# ESP_OBD_Handheld.net
KiCad netlist of a schematic drawn in Altium Designer
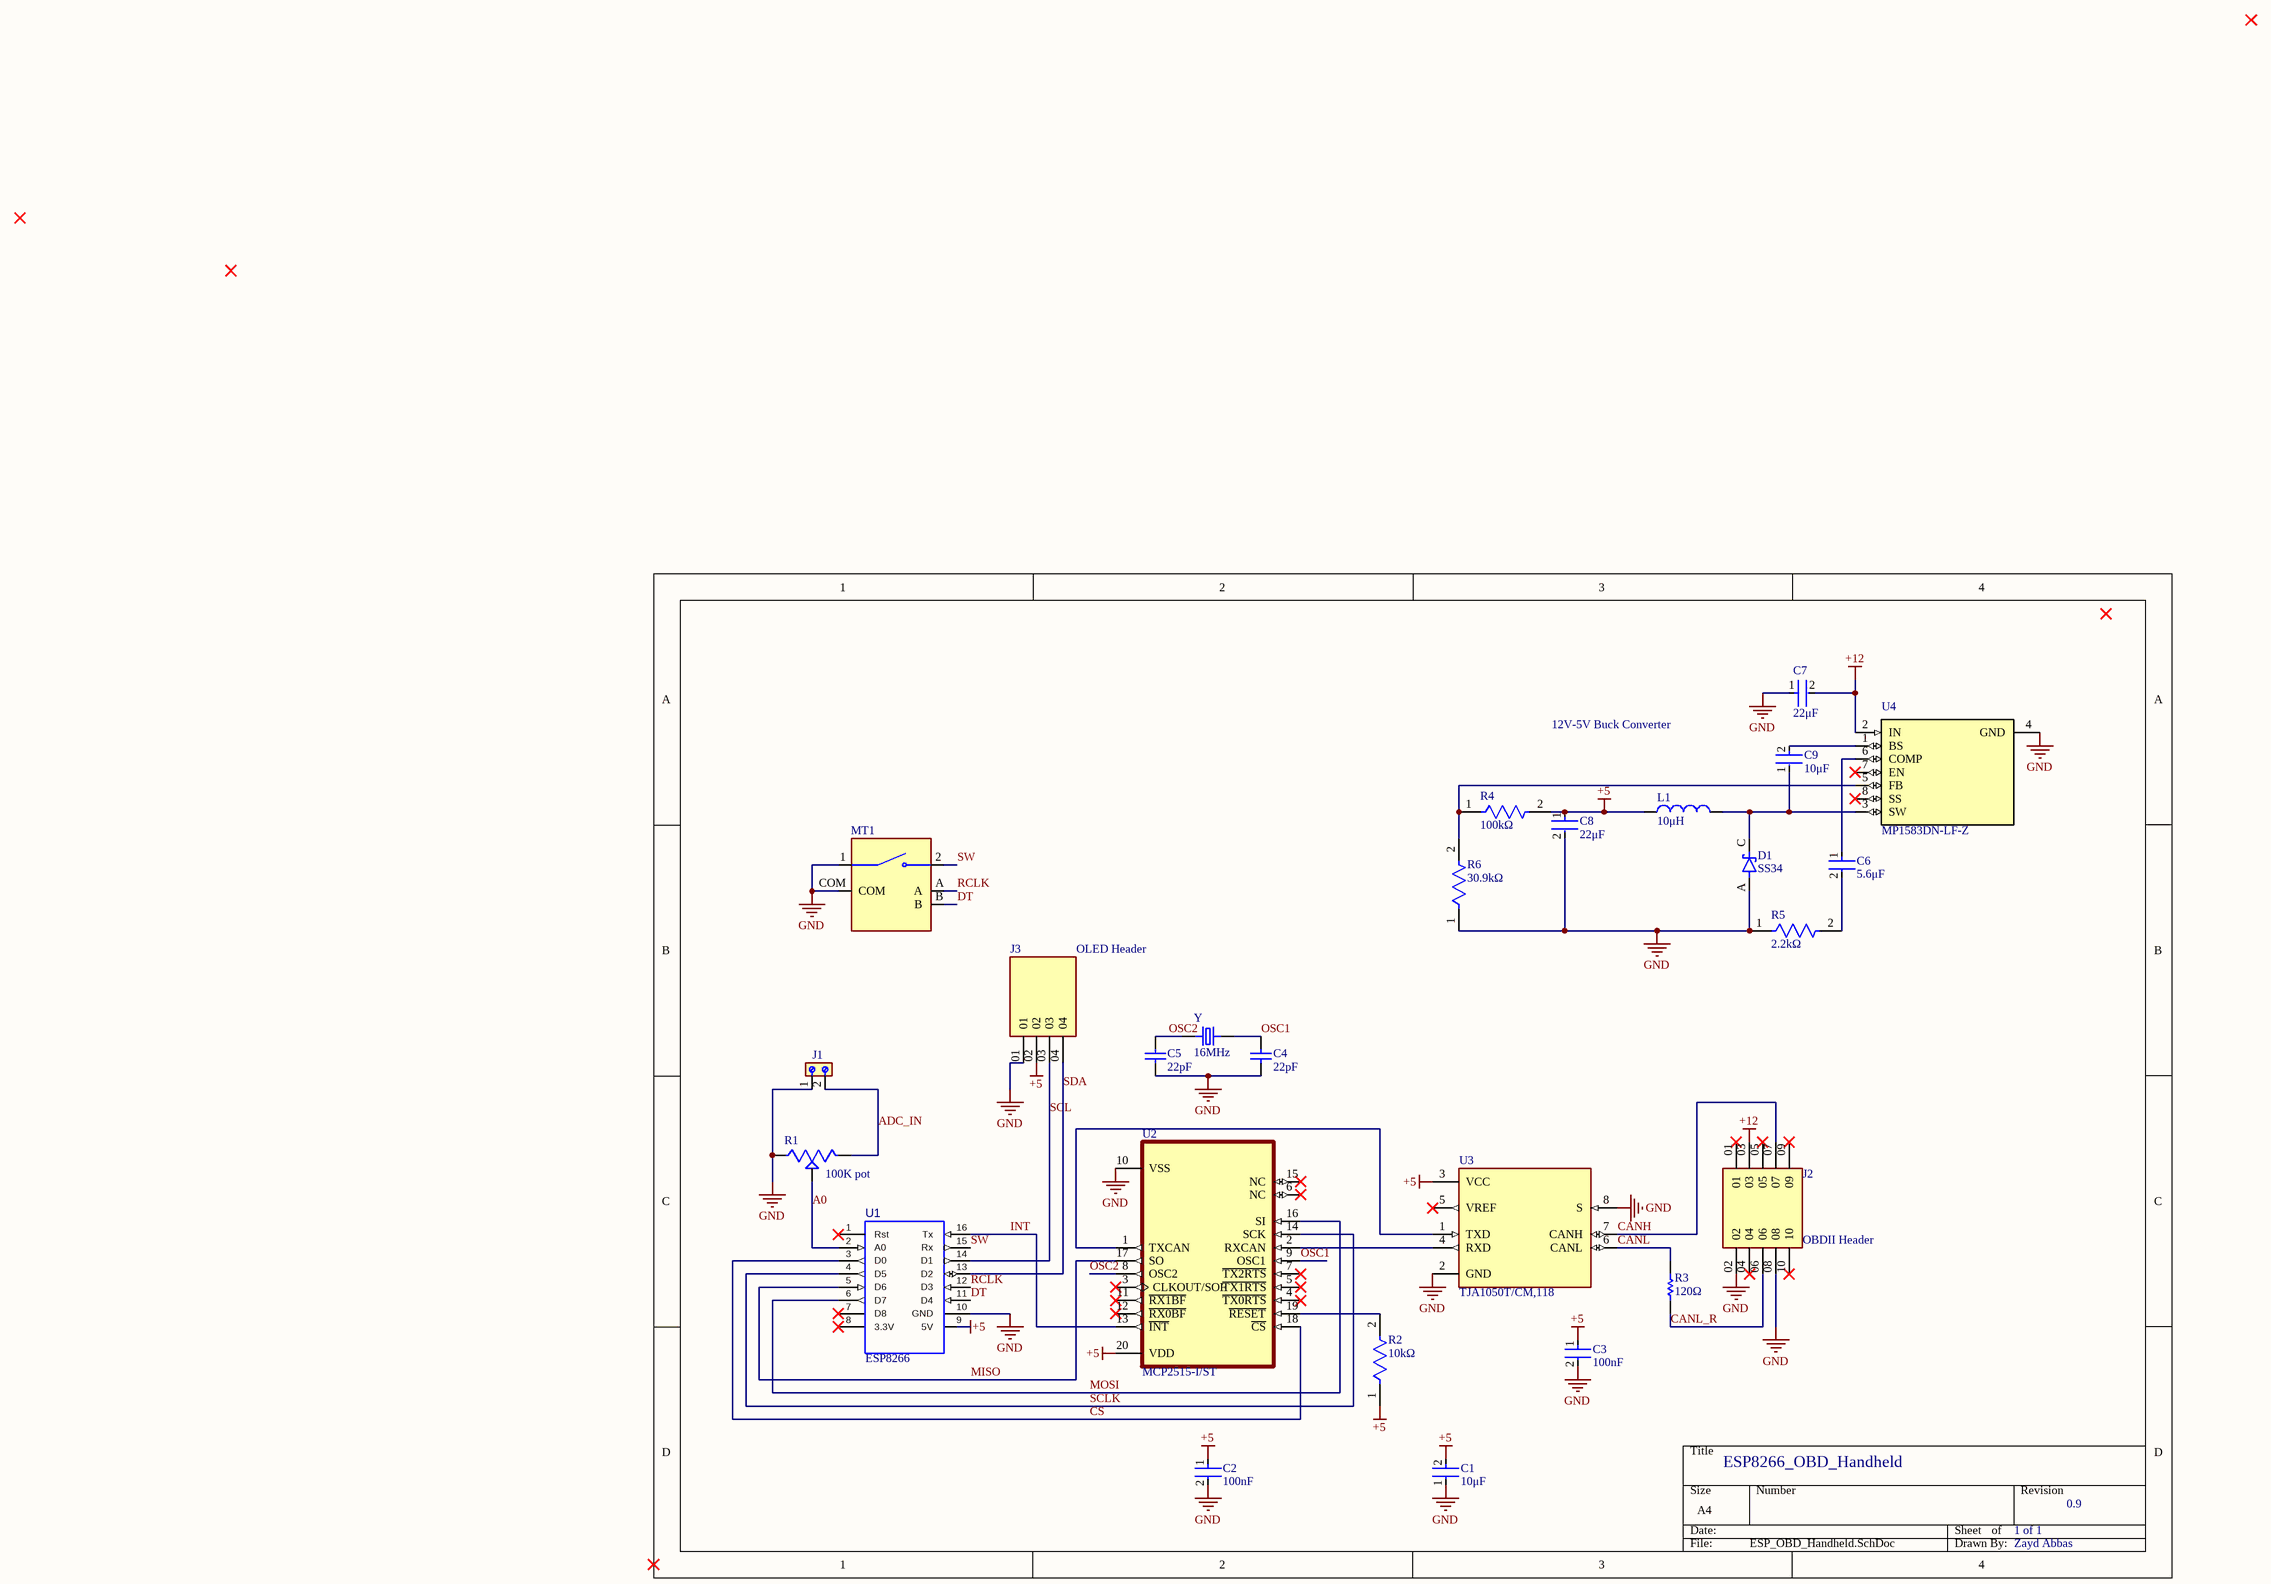
[diagram p0: ESP_OBD_Handheld.SchDoc]

(export (version "E")
  (design (tool "Eeschema 10.0.6"))
  (components
    (comp (ref "C1")
      (value "10μF")
      (footprint "FP-C1608-080-0_1-MFG")
      (description "Multilayer Ceramic Capacitors 10μF ±10% 10V X5R SMD 0603")
      (fields (field (name "VOLTAGE") "10V") (field (name "TOLERANCE") "10%"))
      (libsource (lib "Components - 15.01.23 - 12.48") (part "CMP-2000-04979-3"))
    )
    (comp (ref "C2")
      (value "100nF")
      (footprint "FP-CGA3E-0_3-0_1-IPC_C")
      (description "Cap Ceramic 100nF 50V X7R 10% Pad SMD 0603 +125°C Automotive T/R")
      (fields (field (name "TOLERANCE") "10%") (field (name "VOLTAGE") "50V"))
      (libsource (lib "Components - 15.01.23 - 13.18") (part "CMP-2000-07546-2"))
    )
    (comp (ref "C3")
      (value "100nF")
      (footprint "FP-CGA3E-0_3-0_1-IPC_C")
      (description "Cap Ceramic 100nF 50V X7R 10% Pad SMD 0603 +125°C Automotive T/R")
      (fields (field (name "TOLERANCE") "10%") (field (name "VOLTAGE") "50V"))
      (libsource (lib "Components - 15.01.23 - 13.18") (part "CMP-2000-07546-2"))
    )
    (comp (ref "C4")
      (value "22pF")
      (footprint "CAPC1608X90X35LL10T15")
      (description "Chip Capacitor, 22 pF, +/- 5%, 50 V, -55 to 125 degC, 0603 (1608 Metric), RoHS, Tape and Reel")
      (fields (field (name "MANUFACTURER") "Murata"))
      (libsource (lib "Components - 15.01.23 - 02.22") (part "CMP-2000-04945-1"))
    )
    (comp (ref "C5")
      (value "22pF")
      (footprint "CAPC1608X90X35LL10T15")
      (description "Chip Capacitor, 22 pF, +/- 5%, 50 V, -55 to 125 degC, 0603 (1608 Metric), RoHS, Tape and Reel")
      (fields (field (name "MANUFACTURER") "Murata"))
      (libsource (lib "Components - 15.01.23 - 02.22") (part "CMP-2000-04945-1"))
    )
    (comp (ref "C6")
      (value "5.6μF")
      (footprint "FP-CC0603-DA-IPC_B")
      (description "Surface Mount Ceramic Multilayer Capacitor 0.0056uF 10% X7R 50V 0603 Paper T/R")
      (fields
        (field (name "MANUFACTURER PART NUMBER") "CC0603KRX7R9BB562")
        (field (name "MANUFACTURER") "YAGEO")
      )
      (libsource (lib "Components - 15.01.23 - 13.23") (part "CMP-03422-001341-1"))
    )
    (comp (ref "C7")
      (value "22μF")
      (footprint "FP-C2012-125-0_2-MFG")
      (description "Multilayer Ceramic Capacitors 22μF ±10% 16V X5R SMD 0805")
      (fields (field (name "TOLERANCE") "10%") (field (name "VOLTAGE") "16V"))
      (libsource (lib "Components - 15.01.23 - 13.25") (part "CMP-2000-06037-3"))
    )
    (comp (ref "C8")
      (value "22μF")
      (footprint "FP-C2012-125-0_2-MFG")
      (description "Multilayer Ceramic Capacitors 22μF ±10% 16V X5R SMD 0805")
      (fields (field (name "TOLERANCE") "10%") (field (name "VOLTAGE") "16V"))
      (libsource (lib "Components - 15.01.23 - 13.25") (part "CMP-2000-06037-3"))
    )
    (comp (ref "C9")
      (value "10μF")
      (footprint "FP-C1608-080-0_1-MFG")
      (description "Multilayer Ceramic Capacitors 10μF ±10% 10V X5R SMD 0603")
      (fields (field (name "VOLTAGE") "10V") (field (name "TOLERANCE") "10%"))
      (libsource (lib "Components - 15.01.23 - 12.48") (part "CMP-2000-04979-3"))
    )
    (comp (ref "D1")
      (value "SS34")
      (footprint "DIOM7959X265N")
      (description "Diode Schottky 40 V 3A Surface Mount SMC (DO-214AB)")
      (fields (field (name "MF") "ON Semiconductor"))
      (libsource (lib "SS34") (part "SS34"))
    )
    (comp (ref "J1")
      (value "691102710002")
      (footprint "691102710002")
      (description "2 Position Wire to Board Terminal Block Horizontal with Board 0.197 (5.00mm) Through Hole")
      (fields (field (name "MF") "Wurth Elektronik"))
      (libsource (lib "691102710002") (part "691102710002"))
    )
    (comp (ref "J2")
      (value "TSW-105-05-G-D")
      (footprint "SAMTEC_TSW-105-05-G-D")
      (fields (field (name "MF") "Samtec"))
      (libsource (lib "TSW-105-05-G-D") (part "TSW-105-05-G-D"))
    )
    (comp (ref "J3")
      (value "TLW-104-05-G-S")
      (footprint "SAMTEC_TLW-104-05-G-S")
      (libsource (lib "TLW-104-05-G-S") (part "TLW-104-05-G-S"))
    )
    (comp (ref "L1")
      (value "10μH")
      (footprint "VISH-IHLP2525C-01_V")
      (fields (field (name "MANUFACTURER") "Vishay") (field (name "TOLERANCE") "20%"))
      (libsource (lib "Components - 15.01.23 - 12.38") (part "CMP-2000-06440-1"))
    )
    (comp (ref "MT1")
      (value "PEC11R-4215F-S0024")
      (footprint "XDCR_PEC11R-4215F-S0024")
      (description "Incremental Encoder, 12 Mm, Contact Rating 10 Ma - 5 Vdc")
      (libsource (lib "PEC11R-4215F-S0024") (part "PEC11R-4215F-S0024"))
    )
    (comp (ref "R1")
      (value "100K pot")
      (footprint "TRIM_3296P-1-104LF")
      (description "100 kOhms 0.5W, 1/2W PC Pins Through Hole Trimmer Potentiometer Cermet 25.0 Turn Side Adjustment")
      (fields (field (name "MF") "Bourns") (field (name "MP") "3296P-1-104LF"))
      (libsource (lib "3296P-1-104LF") (part "3296P-1-104LF"))
    )
    (comp (ref "R2")
      (value "10kΩ")
      (footprint "FP-RC0603-0_55-IPC_B")
      (description "RES 10K OHM 1% 1/10W 0603")
      (fields (field (name "TOLERANCE") "1%"))
      (libsource (lib "Components - 15.01.23 - 13.33") (part "CMP-2100-03664-2"))
    )
    (comp (ref "R3")
      (value "120Ω")
      (footprint "RESC1609X55X30LL15T15")
      (description "Chip Resistor, 120 Ohm, +/- 1%, 0.1 W, -55 to 155 degC, 0603 (1608 Metric), RoHS, Tape and Reel")
      (fields (field (name "TOLERANCE") "1%") (field (name "MANUFACTURER") "Panasonic"))
      (libsource (lib "Components - 15.01.23 - 04.22") (part "CMP-2000-00213-2"))
    )
    (comp (ref "R4")
      (value "100kΩ")
      (footprint "FP-RC0603-0_55-MFG")
      (description "RES SMD 100K OHM 1% 1/10W 0603")
      (fields (field (name "TOLERANCE") "1%"))
      (libsource (lib "Components - 15.01.23 - 04.51") (part "CMP-2100-03662-2"))
    )
    (comp (ref "R5")
      (value "2.2kΩ")
      (footprint "FP-AC0603-IPC_C")
      (description "RES 2.2KΩ 1.00% 0.1W 0603")
      (fields (field (name "TOLERANCE") "1%"))
      (libsource (lib "Components - 15.01.23 - 04.54") (part "CMP-2000-04835-3"))
    )
    (comp (ref "R6")
      (value "30.9kΩ")
      (footprint "FP-RT0603-IPC_C")
      (description "RES SMD 30.9K OHM 0.1% 1/10W")
      (fields
        (field (name "MANUFACTURER") "Yageo")
        (field (name "OCTOPART") "https://octopart.com/rt0603brd0730k9l-yageo-1244231")
      )
      (libsource (lib "Components - 15.01.23 - 05.07") (part "CMP-03412-016275-1"))
    )
    (comp (ref "U1")
      (value "ESP8266")
      (footprint "wemos-d1-mini-with-pin-header-and-connector")
      (libsource (lib "D1 Mini") (part "WeMos_D1_mini"))
    )
    (comp (ref "U2")
      (value "MCP2515-I/ST")
      (footprint "SOP65P640X110-20N")
      (description "CANbus Controller CAN 2.0 SPI Interface 20-TSSOP")
      (fields (field (name "MF") "Microchip"))
      (libsource (lib "MCP2515-I_ST") (part "MCP2515-I/ST"))
    )
    (comp (ref "U3")
      (value "TJA1050T/CM,118")
      (footprint "SOIC127P600X175-8N")
      (description "1/1 Transceiver Half CANbus 8-SO")
      (fields (field (name "MF") "NXP USA"))
      (libsource (lib "TJA1050T_CM_118") (part "TJA1050T/CM,118"))
    )
    (comp (ref "U4")
      (value "MP1583DN-LF-Z")
      (footprint "*SOIC127P600X170-9N")
      (libsource (lib "MP1583DN-LF-Z") (part "MP1583DN-LF-Z"))
    )
    (comp (ref "Y")
      (value "16MHz")
      (footprint "XTAL_ECS-160-20-4X")
      (description "16MHz Â±30ppm Crystal Series 40 Ohms HC-49/US")
      (fields (field (name "MF") "ECS Inc.") (field (name "MP") "ECS-160-S-4"))
      (libsource (lib "ECS-160-S-4") (part "ECS-160-S-4"))
    )
  )
  (nets
    (net (code "1") (name "+5") (class "Default")
      (node (ref "C1") (pin "2") (pinfunction "2_2") (pintype "passive"))
      (node (ref "C2") (pin "1") (pinfunction "1_1") (pintype "passive"))
      (node (ref "C3") (pin "1") (pinfunction "1_1") (pintype "passive"))
      (node (ref "C8") (pin "1") (pinfunction "1_1") (pintype "passive"))
      (node (ref "J3") (pin "02") (pinfunction "02_02") (pintype "passive"))
      (node (ref "L1") (pin "1") (pinfunction "1_1") (pintype "passive"))
      (node (ref "R2") (pin "1") (pinfunction "1_1") (pintype "passive"))
      (node (ref "R4") (pin "2") (pinfunction "2_2") (pintype "passive"))
      (node (ref "U1") (pin "9") (pinfunction "5V_9") (pintype "power_in"))
      (node (ref "U2") (pin "20") (pinfunction "VDD_20") (pintype "power_in"))
      (node (ref "U3") (pin "3") (pinfunction "VCC_3") (pintype "power_in"))
    )
    (net (code "2") (name "+12") (class "Default")
      (node (ref "C7") (pin "2") (pinfunction "2_2") (pintype "passive"))
      (node (ref "J2") (pin "03") (pinfunction "03_03") (pintype "passive"))
      (node (ref "U4") (pin "2") (pinfunction "IN_2") (pintype "input"))
    )
    (net (code "3") (name "/A0") (class "Default")
      (node (ref "R1") (pin "2") (pinfunction "WIPER_2") (pintype "passive"))
      (node (ref "U1") (pin "2") (pinfunction "A0_2") (pintype "input"))
    )
    (net (code "4") (name "/ADC_IN") (class "Default")
      (node (ref "J1") (pin "2") (pinfunction "2_2") (pintype "passive"))
      (node (ref "R1") (pin "3") (pinfunction "CW_3") (pintype "passive"))
    )
    (net (code "5") (name "/CANH") (class "Default")
      (node (ref "J2") (pin "07") (pinfunction "07_07") (pintype "passive"))
      (node (ref "U3") (pin "7") (pinfunction "CANH_7") (pintype "bidirectional"))
    )
    (net (code "6") (name "/CANL") (class "Default")
      (node (ref "R3") (pin "1") (pinfunction "1_1") (pintype "passive"))
      (node (ref "U3") (pin "6") (pinfunction "CANL_6") (pintype "bidirectional"))
    )
    (net (code "7") (name "/CANL_R") (class "Default")
      (node (ref "J2") (pin "06") (pinfunction "06_06") (pintype "passive"))
      (node (ref "R3") (pin "2") (pinfunction "2_2") (pintype "passive"))
    )
    (net (code "8") (name "/CS") (class "Default")
      (node (ref "U1") (pin "3") (pinfunction "D0_3") (pintype "output"))
      (node (ref "U2") (pin "18") (pinfunction "~{CS}_18") (pintype "input"))
    )
    (net (code "9") (name "/DT") (class "Default")
      (node (ref "MT1") (pin "B") (pinfunction "B_B") (pintype "passive"))
      (node (ref "U1") (pin "11") (pinfunction "D4_11") (pintype "input"))
    )
    (net (code "10") (name "/INT") (class "Default")
      (node (ref "U1") (pin "16") (pinfunction "Tx_16") (pintype "input"))
      (node (ref "U2") (pin "13") (pinfunction "~{INT}_13") (pintype "output"))
    )
    (net (code "11") (name "/MISO") (class "Default")
      (node (ref "U1") (pin "5") (pinfunction "D6_5") (pintype "input"))
      (node (ref "U2") (pin "17") (pinfunction "SO_17") (pintype "output"))
    )
    (net (code "12") (name "/MOSI") (class "Default")
      (node (ref "U1") (pin "6") (pinfunction "D7_6") (pintype "output"))
      (node (ref "U2") (pin "16") (pinfunction "SI_16") (pintype "input"))
    )
    (net (code "13") (name "/OSC1") (class "Default")
      (node (ref "C4") (pin "2") (pinfunction "2_2") (pintype "passive"))
      (node (ref "U2") (pin "9") (pinfunction "OSC1_9") (pintype "input"))
      (node (ref "Y") (pin "2") (pinfunction "2_2") (pintype "passive"))
    )
    (net (code "14") (name "/OSC2") (class "Default")
      (node (ref "C5") (pin "2") (pinfunction "2_2") (pintype "passive"))
      (node (ref "U2") (pin "8") (pinfunction "OSC2_8") (pintype "output"))
      (node (ref "Y") (pin "1") (pinfunction "1_1") (pintype "passive"))
    )
    (net (code "15") (name "/RCLK") (class "Default")
      (node (ref "MT1") (pin "A") (pinfunction "A_A") (pintype "passive"))
      (node (ref "U1") (pin "12") (pinfunction "D3_12") (pintype "input"))
    )
    (net (code "16") (name "/SCL") (class "Default")
      (node (ref "J3") (pin "03") (pinfunction "03_03") (pintype "passive"))
      (node (ref "U1") (pin "14") (pinfunction "D1_14") (pintype "output"))
    )
    (net (code "17") (name "/SCLK") (class "Default")
      (node (ref "U1") (pin "4") (pinfunction "D5_4") (pintype "output"))
      (node (ref "U2") (pin "14") (pinfunction "SCK_14") (pintype "input"))
    )
    (net (code "18") (name "/SDA") (class "Default")
      (node (ref "J3") (pin "04") (pinfunction "04_04") (pintype "passive"))
      (node (ref "U1") (pin "13") (pinfunction "D2_13") (pintype "bidirectional"))
    )
    (net (code "19") (name "/SW") (class "Default")
      (node (ref "MT1") (pin "2") (pinfunction "2_2") (pintype "passive"))
      (node (ref "U1") (pin "15") (pinfunction "Rx_15") (pintype "output"))
    )
    (net (code "20") (name "GND") (class "Default")
      (node (ref "C1") (pin "1") (pinfunction "1_1") (pintype "passive"))
      (node (ref "C2") (pin "2") (pinfunction "2_2") (pintype "passive"))
      (node (ref "C3") (pin "2") (pinfunction "2_2") (pintype "passive"))
      (node (ref "C4") (pin "1") (pinfunction "1_1") (pintype "passive"))
      (node (ref "C5") (pin "1") (pinfunction "1_1") (pintype "passive"))
      (node (ref "C7") (pin "1") (pinfunction "1_1") (pintype "passive"))
      (node (ref "C8") (pin "2") (pinfunction "2_2") (pintype "passive"))
      (node (ref "D1") (pin "A") (pinfunction "A_A") (pintype "passive"))
      (node (ref "J1") (pin "1") (pinfunction "1_1") (pintype "passive"))
      (node (ref "J2") (pin "02") (pinfunction "02_02") (pintype "passive"))
      (node (ref "J2") (pin "08") (pinfunction "08_08") (pintype "passive"))
      (node (ref "J3") (pin "01") (pinfunction "01_01") (pintype "passive"))
      (node (ref "MT1") (pin "1") (pinfunction "1_1") (pintype "passive"))
      (node (ref "MT1") (pin "COM") (pinfunction "COM_COM") (pintype "passive"))
      (node (ref "R1") (pin "1") (pinfunction "CCW_1") (pintype "passive"))
      (node (ref "R5") (pin "1") (pinfunction "1_1") (pintype "passive"))
      (node (ref "R6") (pin "1") (pinfunction "1_1") (pintype "passive"))
      (node (ref "U1") (pin "10") (pinfunction "GND_10") (pintype "power_in"))
      (node (ref "U2") (pin "10") (pinfunction "VSS_10") (pintype "power_in"))
      (node (ref "U3") (pin "2") (pinfunction "GND_2") (pintype "power_in"))
      (node (ref "U3") (pin "8") (pinfunction "S_8") (pintype "input"))
      (node (ref "U4") (pin "4") (pinfunction "GND_4") (pintype "power_in"))
    )
    (net (code "21") (name "Net-(C6-Pad2)") (class "Default")
      (node (ref "C6") (pin "2") (pinfunction "2_2") (pintype "passive"))
      (node (ref "R5") (pin "2") (pinfunction "2_2") (pintype "passive"))
    )
    (net (code "22") (name "Net-(D1-K)") (class "Default")
      (node (ref "C9") (pin "1") (pinfunction "1_1") (pintype "passive"))
      (node (ref "D1") (pin "C") (pinfunction "K_C") (pintype "passive"))
      (node (ref "L1") (pin "2") (pinfunction "2_2") (pintype "passive"))
      (node (ref "U4") (pin "3") (pinfunction "SW_3") (pintype "bidirectional"))
    )
    (net (code "23") (name "Net-(U2-RXCAN)") (class "Default")
      (node (ref "U2") (pin "2") (pinfunction "RXCAN_2") (pintype "input"))
      (node (ref "U3") (pin "4") (pinfunction "RXD_4") (pintype "output"))
    )
    (net (code "24") (name "Net-(U2-TXCAN)") (class "Default")
      (node (ref "U2") (pin "1") (pinfunction "TXCAN_1") (pintype "output"))
      (node (ref "U3") (pin "1") (pinfunction "TXD_1") (pintype "input"))
    )
    (net (code "25") (name "Net-(U2-~{RESET})") (class "Default")
      (node (ref "R2") (pin "2") (pinfunction "2_2") (pintype "passive"))
      (node (ref "U2") (pin "19") (pinfunction "~{RESET}_19") (pintype "input"))
    )
    (net (code "26") (name "Net-(U4-BS)") (class "Default")
      (node (ref "C9") (pin "2") (pinfunction "2_2") (pintype "passive"))
      (node (ref "U4") (pin "1") (pinfunction "BS_1") (pintype "bidirectional"))
    )
    (net (code "27") (name "Net-(U4-COMP)") (class "Default")
      (node (ref "C6") (pin "1") (pinfunction "1_1") (pintype "passive"))
      (node (ref "U4") (pin "6") (pinfunction "COMP_6") (pintype "bidirectional"))
    )
    (net (code "28") (name "Net-(U4-FB)") (class "Default")
      (node (ref "R4") (pin "1") (pinfunction "1_1") (pintype "passive"))
      (node (ref "R6") (pin "2") (pinfunction "2_2") (pintype "passive"))
      (node (ref "U4") (pin "5") (pinfunction "FB_5") (pintype "bidirectional"))
    )
    (net (code "29") (name "unconnected-(J2-Pad01)") (class "Default")
      (node (ref "J2") (pin "01") (pinfunction "01_01") (pintype "passive+no_connect"))
    )
    (net (code "30") (name "unconnected-(J2-Pad04)") (class "Default")
      (node (ref "J2") (pin "04") (pinfunction "04_04") (pintype "passive+no_connect"))
    )
    (net (code "31") (name "unconnected-(J2-Pad05)") (class "Default")
      (node (ref "J2") (pin "05") (pinfunction "05_05") (pintype "passive+no_connect"))
    )
    (net (code "32") (name "unconnected-(J2-Pad09)") (class "Default")
      (node (ref "J2") (pin "09") (pinfunction "09_09") (pintype "passive+no_connect"))
    )
    (net (code "33") (name "unconnected-(J2-Pad10)") (class "Default")
      (node (ref "J2") (pin "10") (pinfunction "10_10") (pintype "passive+no_connect"))
    )
    (net (code "34") (name "unconnected-(U1-3.3V-Pad8)") (class "Default")
      (node (ref "U1") (pin "8") (pinfunction "3.3V_8") (pintype "power_in+no_connect"))
    )
    (net (code "35") (name "unconnected-(U1-D8-Pad7)") (class "Default")
      (node (ref "U1") (pin "7") (pinfunction "D8_7") (pintype "passive+no_connect"))
    )
    (net (code "36") (name "unconnected-(U1-Rst-Pad1)") (class "Default")
      (node (ref "U1") (pin "1") (pinfunction "Rst_1") (pintype "passive+no_connect"))
    )
    (net (code "37") (name "unconnected-(U2-CLKOUT{slash}SOF-Pad3)") (class "Default")
      (node (ref "U2") (pin "3") (pinfunction "CLKOUT/SOF_3") (pintype "output+no_connect"))
    )
    (net (code "38") (name "unconnected-(U2-NC-Pad6)") (class "Default")
      (node (ref "U2") (pin "6") (pinfunction "NC_6") (pintype "bidirectional+no_connect"))
    )
    (net (code "39") (name "unconnected-(U2-NC-Pad15)") (class "Default")
      (node (ref "U2") (pin "15") (pinfunction "NC_15") (pintype "bidirectional+no_connect"))
    )
    (net (code "40") (name "unconnected-(U2-~{RX0BF}-Pad12)") (class "Default")
      (node (ref "U2") (pin "12") (pinfunction "~{RX0BF}_12") (pintype "output+no_connect"))
    )
    (net (code "41") (name "unconnected-(U2-~{RX1BF}-Pad11)") (class "Default")
      (node (ref "U2") (pin "11") (pinfunction "~{RX1BF}_11") (pintype "output+no_connect"))
    )
    (net (code "42") (name "unconnected-(U2-~{TX0RTS}-Pad4)") (class "Default")
      (node (ref "U2") (pin "4") (pinfunction "~{TX0RTS}_4") (pintype "input+no_connect"))
    )
    (net (code "43") (name "unconnected-(U2-~{TX1RTS}-Pad5)") (class "Default")
      (node (ref "U2") (pin "5") (pinfunction "~{TX1RTS}_5") (pintype "input+no_connect"))
    )
    (net (code "44") (name "unconnected-(U2-~{TX2RTS}-Pad7)") (class "Default")
      (node (ref "U2") (pin "7") (pinfunction "~{TX2RTS}_7") (pintype "input+no_connect"))
    )
    (net (code "45") (name "unconnected-(U3-VREF-Pad5)") (class "Default")
      (node (ref "U3") (pin "5") (pinfunction "VREF_5") (pintype "output+no_connect"))
    )
    (net (code "46") (name "unconnected-(U4-EN-Pad7)") (class "Default")
      (node (ref "U4") (pin "7") (pinfunction "EN_7") (pintype "bidirectional+no_connect"))
    )
    (net (code "47") (name "unconnected-(U4-SS-Pad8)") (class "Default")
      (node (ref "U4") (pin "8") (pinfunction "SS_8") (pintype "bidirectional+no_connect"))
    )
  )
)
